# battery-bulb.net
KiCad netlist of a schematic drawn in EAGLE
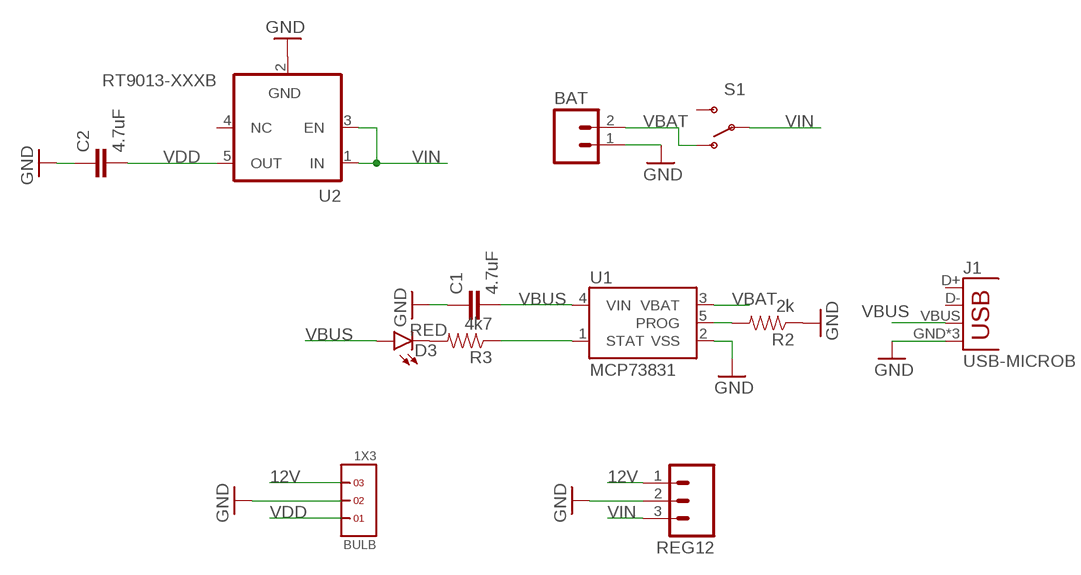
[diagram p0: schematic, sheet 1]

(export (version "E")
  (design (tool "Eeschema 10.0.6"))
  (components
    (comp (ref "BAT")
      (value "M02JST-PTH-2")
      (footprint "eagle-import:JST-2-PTH")
      (libsource (lib "eagle-import") (part "M02JST-PTH-2"))
    )
    (comp (ref "BULB")
      (value "1X3")
      (footprint "eagle-import:1X3")
      (libsource (lib "eagle-import") (part "1X3"))
    )
    (comp (ref "C1")
      (value "4.7uF")
      (footprint "eagle-import:0603-CAP")
      (libsource (lib "eagle-import") (part "CAP0603-CAP"))
    )
    (comp (ref "C2")
      (value "4.7uF")
      (footprint "eagle-import:0603-CAP")
      (libsource (lib "eagle-import") (part "CAP0603-CAP"))
    )
    (comp (ref "D3")
      (value "RED")
      (footprint "eagle-import:LED-0603")
      (libsource (lib "eagle-import") (part "LED-RED0603"))
    )
    (comp (ref "J1")
      (value "USB-MICROB")
      (footprint "eagle-import:USB-MICROB")
      (libsource (lib "eagle-import") (part "USB-MICROB"))
    )
    (comp (ref "R2")
      (value "2k")
      (footprint "eagle-import:0603-RES")
      (libsource (lib "eagle-import") (part "4.7OHM-1/10W-5%(0603)"))
    )
    (comp (ref "R3")
      (value "4k7")
      (footprint "eagle-import:0603-RES")
      (libsource (lib "eagle-import") (part "4.7OHM-1/10W-5%(0603)"))
    )
    (comp (ref "REG12")
      (value "M03LOCK")
      (footprint "eagle-import:1X03_LOCK")
      (libsource (lib "eagle-import") (part "M03LOCK"))
    )
    (comp (ref "S1")
      (value "SWITCH-SPDT-SMD-A")
      (footprint "eagle-import:SWITCH-SPST-SMD-A")
      (libsource (lib "eagle-import") (part "SWITCH-SPDT-SMD-A"))
    )
    (comp (ref "U1")
      (value "MCP73831")
      (footprint "eagle-import:SOT23-5")
      (libsource (lib "eagle-import") (part "MCP73831"))
    )
    (comp (ref "U2")
      (value "RT9013-XXXB")
      (footprint "eagle-import:SOT23-5")
      (libsource (lib "eagle-import") (part "RT9013-XXXB"))
    )
  )
  (nets
    (net (code "1") (name "/12V") (class "Default")
      (node (ref "BULB") (pin "3") (pinfunction "3_3") (pintype "bidirectional"))
      (node (ref "REG12") (pin "1") (pinfunction "1_1") (pintype "passive"))
    )
    (net (code "2") (name "/VBAT") (class "Default")
      (node (ref "BAT") (pin "2") (pinfunction "2_2") (pintype "passive"))
      (node (ref "S1") (pin "1") (pinfunction "O_1") (pintype "passive"))
      (node (ref "U1") (pin "3") (pinfunction "VBAT_3") (pintype "power_in"))
    )
    (net (code "3") (name "/VBUS") (class "Default")
      (node (ref "C1") (pin "2") (pinfunction "2_2") (pintype "passive"))
      (node (ref "D3") (pin "A") (pinfunction "A_A") (pintype "passive"))
      (node (ref "J1") (pin "VBUS") (pinfunction "VBUS_VBUS") (pintype "bidirectional"))
      (node (ref "U1") (pin "4") (pinfunction "VIN_4") (pintype "power_in"))
    )
    (net (code "4") (name "/VDD") (class "Default")
      (node (ref "BULB") (pin "1") (pinfunction "1_1") (pintype "bidirectional"))
      (node (ref "C2") (pin "2") (pinfunction "2_2") (pintype "passive"))
      (node (ref "U2") (pin "5") (pinfunction "OUT_5") (pintype "passive"))
    )
    (net (code "5") (name "/VIN") (class "Default")
      (node (ref "REG12") (pin "3") (pinfunction "3_3") (pintype "passive"))
      (node (ref "S1") (pin "2") (pinfunction "P_2") (pintype "passive"))
      (node (ref "U2") (pin "1") (pinfunction "IN_1") (pintype "input"))
      (node (ref "U2") (pin "3") (pinfunction "EN_3") (pintype "input"))
    )
    (net (code "6") (name "GND") (class "Default")
      (node (ref "BAT") (pin "1") (pinfunction "1_1") (pintype "passive"))
      (node (ref "BULB") (pin "2") (pinfunction "2_2") (pintype "bidirectional"))
      (node (ref "C1") (pin "1") (pinfunction "1_1") (pintype "passive"))
      (node (ref "C2") (pin "1") (pinfunction "1_1") (pintype "passive"))
      (node (ref "J1") (pin "GND") (pinfunction "GND_GND") (pintype "bidirectional"))
      (node (ref "J1") (pin "MT1") (pinfunction "GND_MT1") (pintype "bidirectional"))
      (node (ref "J1") (pin "MT2") (pinfunction "GND_MT2") (pintype "bidirectional"))
      (node (ref "R2") (pin "1") (pinfunction "1_1") (pintype "passive"))
      (node (ref "REG12") (pin "2") (pinfunction "2_2") (pintype "passive"))
      (node (ref "U1") (pin "2") (pinfunction "VSS_2") (pintype "power_in"))
      (node (ref "U2") (pin "2") (pinfunction "GND_2") (pintype "power_in"))
    )
    (net (code "7") (name "Net-(D3-PadC)") (class "Default")
      (node (ref "D3") (pin "C") (pinfunction "C_C") (pintype "passive"))
      (node (ref "R3") (pin "2") (pinfunction "2_2") (pintype "passive"))
    )
    (net (code "8") (name "Net-(U1-PROG)") (class "Default")
      (node (ref "R2") (pin "2") (pinfunction "2_2") (pintype "passive"))
      (node (ref "U1") (pin "5") (pinfunction "PROG_5") (pintype "input"))
    )
    (net (code "9") (name "Net-(U1-STAT)") (class "Default")
      (node (ref "R3") (pin "1") (pinfunction "1_1") (pintype "passive"))
      (node (ref "U1") (pin "1") (pinfunction "STAT_1") (pintype "output"))
    )
    (net (code "10") (name "unconnected-(J1-PadD+)") (class "Default")
      (node (ref "J1") (pin "D+") (pinfunction "D+_D+") (pintype "bidirectional"))
    )
    (net (code "11") (name "unconnected-(J1-PadD-)") (class "Default")
      (node (ref "J1") (pin "D-") (pinfunction "D-_D-") (pintype "bidirectional"))
    )
    (net (code "12") (name "unconnected-(S1-S-Pad3)") (class "Default")
      (node (ref "S1") (pin "3") (pinfunction "S_3") (pintype "passive"))
    )
    (net (code "13") (name "unconnected-(U2-NC-Pad4)") (class "Default")
      (node (ref "U2") (pin "4") (pinfunction "NC_4") (pintype "no_connect"))
    )
  )
)
